# Servo_Controller_Board.net
KiCad netlist of a schematic drawn in Altium Designer
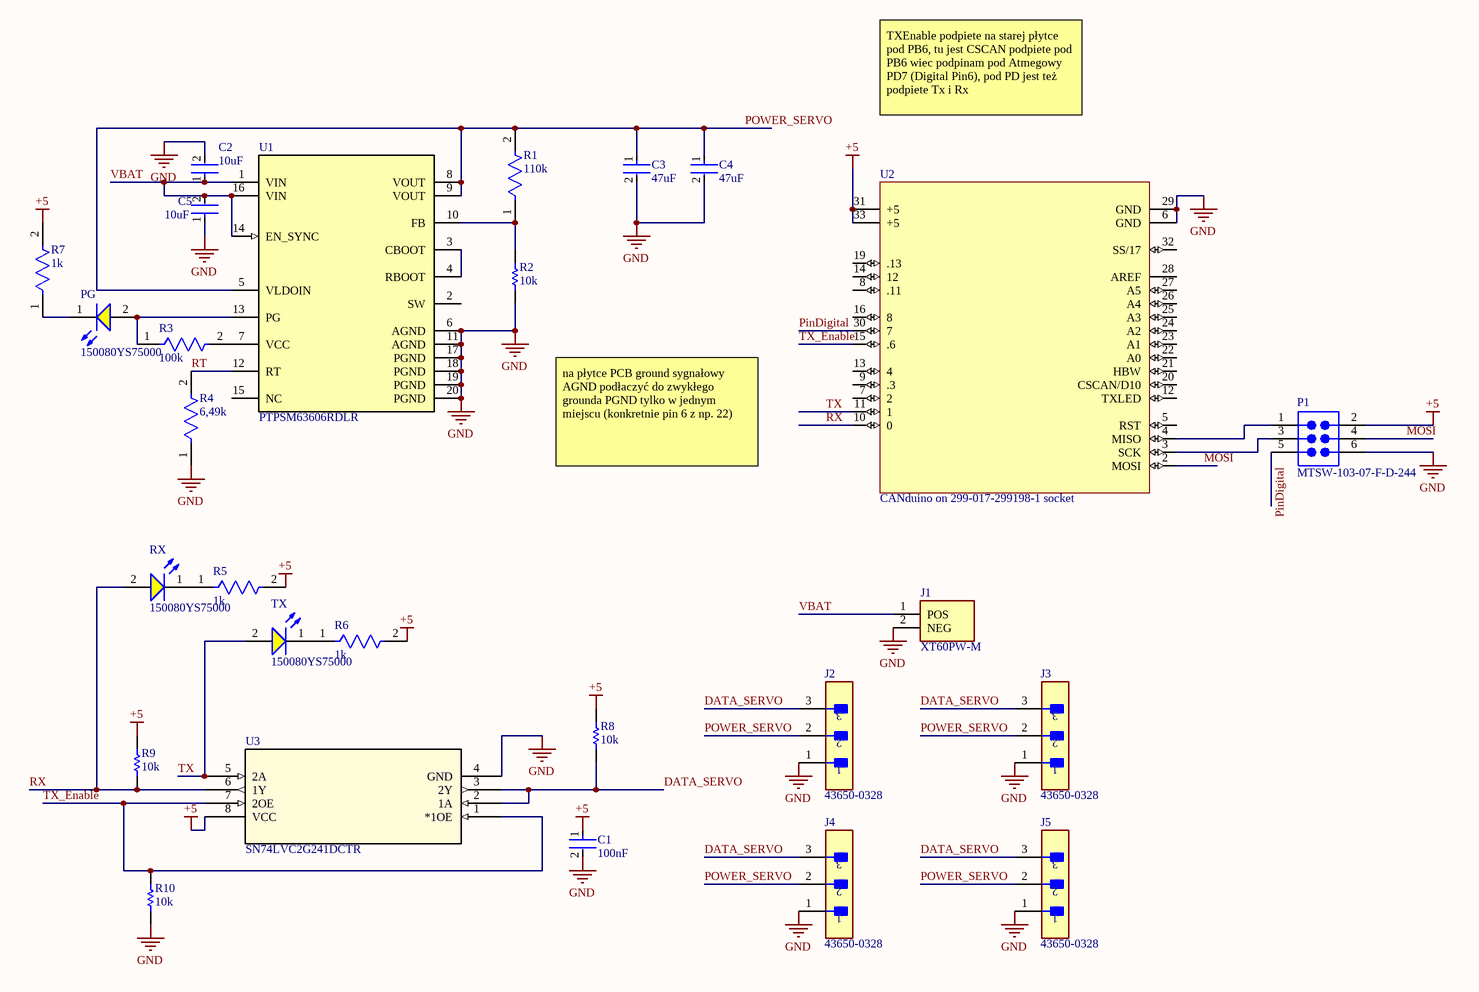
[diagram p0: Servo Controller Board.SchDoc]

(export (version "E")
  (design (tool "Eeschema 10.0.6"))
  (components
    (comp (ref "C1")
      (value "100nF")
      (footprint "FP-0805-L_2_01_0_2-W_1_25-IPC_B")
      (description "Automotive Ceramic Capacitor, 0805, 100nF, 10%, X7R, 15%, 100V")
      (fields (field (name "TOLERANCE") "10%") (field (name "VOLTAGE") "100V"))
      (libsource (lib "Altium Content Vault") (part "b4654b650e69147ec39a6b967a45e02"))
    )
    (comp (ref "C2")
      (value "10uF")
      (footprint "FP-CL32-IPC_A")
      (description "Cap Ceramic 10uF 35V X7R ±10% SMD 1210 +125°C Embossed T/R")
      (fields (field (name "VOLTAGE") "35V") (field (name "TOLERANCE") "10%"))
      (libsource (lib "Altium Content Vault") (part "b4654b650e69147ec39a6b967a45e02"))
    )
    (comp (ref "C3")
      (value "47uF")
      (footprint "FP-GRM32E-0_3-0_2-IPC_A")
      (description "Chip Multilayer Ceramic Capacitors for General Purpose, 1210, 47uF, X6S, 22%, 10%, 16V")
      (fields (field (name "VOLTAGE") "16V") (field (name "TOLERANCE") "10%"))
      (libsource (lib "Altium Content Vault") (part "02cd4be3c70576c341d710602a673aa"))
    )
    (comp (ref "C4")
      (value "47uF")
      (footprint "FP-GRM32E-0_3-0_2-IPC_A")
      (description "Chip Multilayer Ceramic Capacitors for General Purpose, 1210, 47uF, X6S, 22%, 10%, 16V")
      (fields (field (name "VOLTAGE") "16V") (field (name "TOLERANCE") "10%"))
      (libsource (lib "Altium Content Vault") (part "02cd4be3c70576c341d710602a673aa"))
    )
    (comp (ref "C5")
      (value "10uF")
      (footprint "FP-CL32-IPC_A")
      (description "Cap Ceramic 10uF 35V X7R ±10% SMD 1210 +125°C Embossed T/R")
      (fields (field (name "VOLTAGE") "35V") (field (name "TOLERANCE") "10%"))
      (libsource (lib "Altium Content Vault") (part "b4654b650e69147ec39a6b967a45e02"))
    )
    (comp (ref "J1")
      (value "XT60PW-M")
      (footprint "AMASS_XT60PW-M:AMASS_XT60PW-M")
      (description "Socket, DC supply, male, PIN: 2")
      (fields (field (name "MF") "AMASS"))
      (libsource (lib "XT60PW-M") (part "XT60PW-M"))
    )
    (comp (ref "J2")
      (value "43650-0328")
      (footprint "FP-43650-0328-MFG")
      (description "43650-0328 Connector Header HDR 3 POS 3mm Solder ST Thru-Hole 3 Terminal 1 Port Micro-Fit 3.0 Tray")
      (libsource (lib "Altium Content Vault") (part "0d3f023dd272f625e17a2be33dea85f"))
    )
    (comp (ref "J3")
      (value "43650-0328")
      (footprint "FP-43650-0328-MFG")
      (description "43650-0328 Connector Header HDR 3 POS 3mm Solder ST Thru-Hole 3 Terminal 1 Port Micro-Fit 3.0 Tray")
      (libsource (lib "Altium Content Vault") (part "0d3f023dd272f625e17a2be33dea85f"))
    )
    (comp (ref "J4")
      (value "43650-0328")
      (footprint "FP-43650-0328-MFG")
      (description "43650-0328 Connector Header HDR 3 POS 3mm Solder ST Thru-Hole 3 Terminal 1 Port Micro-Fit 3.0 Tray")
      (libsource (lib "Altium Content Vault") (part "0d3f023dd272f625e17a2be33dea85f"))
    )
    (comp (ref "J5")
      (value "43650-0328")
      (footprint "FP-43650-0328-MFG")
      (description "43650-0328 Connector Header HDR 3 POS 3mm Solder ST Thru-Hole 3 Terminal 1 Port Micro-Fit 3.0 Tray")
      (libsource (lib "Altium Content Vault") (part "0d3f023dd272f625e17a2be33dea85f"))
    )
    (comp (ref "P1")
      (value "MTSW-103-07-F-D-244")
      (footprint "SMTC-MTSW-103-07-X-D-244")
      (fields (field (name "MANUFACTURER") "Samtec"))
      (libsource (lib "Altium Content Vault") (part "SMTC-MTSW-103-07-X-D-244"))
    )
    (comp (ref "PG")
      (value "150080YS75000")
      (footprint "WL-SMCW_0805_150080xx75000")
      (description "2 V Yellow LED 2012 (0805) SMD, Wurth Elektronik WL-SMCW 150080YS75000")
      (libsource (lib "Altium Content Vault") (part "LED_Yellow_2A-1K"))
    )
    (comp (ref "R1")
      (value "110k")
      (footprint "FP-AC0603-IPC_B")
      (description "RES 110KΩ 1.00% 0.1W 0603")
      (fields (field (name "TOLERANCE") "1%"))
      (libsource (lib "Altium Content Vault") (part "1029c3af85768c4190bb7ad29bc67b5"))
    )
    (comp (ref "R2")
      (value "10k")
      (footprint "RESC1608X55X25NL10T15")
      (description "Resistor, 10 KOhm, +/- 5%, 100 mW, -55 to 155 degC, 0603 (1608 Metric), RoHS, Tape and Reel")
      (fields (field (name "MANUFACTURER") "Yageo") (field (name "TOLERANCE") "5%"))
      (libsource (lib "Altium Content Vault") (part "RES-2"))
    )
    (comp (ref "R3")
      (value "100k")
      (footprint "FP-AC0603-IPC_B")
      (description "RES 100KΩ 1.00% 0.1W 0603")
      (fields (field (name "TOLERANCE") "1%"))
      (libsource (lib "Altium Content Vault") (part "1029c3af85768c4190bb7ad29bc67b5"))
    )
    (comp (ref "R4")
      (value "6,49k")
      (footprint "FP-CRCW0603-e3-IPC_B")
      (description "RES Thick Film, 6.49kΩ, 1%, 0.1W, 100ppm/°C, 0603")
      (fields (field (name "TOLERANCE") "1%"))
      (libsource (lib "Altium Content Vault") (part "1029c3af85768c4190bb7ad29bc67b5"))
    )
    (comp (ref "R5")
      (value "1k")
      (footprint "FP-RC0603-0_55-IPC_B")
      (description "RES 1K OHM 1% 1/10W 0603")
      (fields (field (name "TOLERANCE") "1%"))
      (libsource (lib "Altium Content Vault") (part "1029c3af85768c4190bb7ad29bc67b5"))
    )
    (comp (ref "R6")
      (value "1k")
      (footprint "FP-RC0603-0_55-IPC_B")
      (description "RES 1K OHM 1% 1/10W 0603")
      (fields (field (name "TOLERANCE") "1%"))
      (libsource (lib "Altium Content Vault") (part "1029c3af85768c4190bb7ad29bc67b5"))
    )
    (comp (ref "R7")
      (value "1k")
      (footprint "FP-RC0603-0_55-IPC_B")
      (description "RES 1K OHM 1% 1/10W 0603")
      (fields (field (name "TOLERANCE") "1%"))
      (libsource (lib "Altium Content Vault") (part "1029c3af85768c4190bb7ad29bc67b5"))
    )
    (comp (ref "R8")
      (value "10k")
      (footprint "RESC1608X55X25NL10T15")
      (description "Resistor, 10 KOhm, +/- 5%, 100 mW, -55 to 155 degC, 0603 (1608 Metric), RoHS, Tape and Reel")
      (fields (field (name "MANUFACTURER") "Yageo") (field (name "TOLERANCE") "5%"))
      (libsource (lib "Altium Content Vault") (part "RES-2"))
    )
    (comp (ref "R9")
      (value "10k")
      (footprint "RESC1608X55X25NL10T15")
      (description "Resistor, 10 KOhm, +/- 5%, 100 mW, -55 to 155 degC, 0603 (1608 Metric), RoHS, Tape and Reel")
      (fields (field (name "MANUFACTURER") "Yageo") (field (name "TOLERANCE") "5%"))
      (libsource (lib "Altium Content Vault") (part "RES-2"))
    )
    (comp (ref "R10")
      (value "10k")
      (footprint "RESC1608X55X25NL10T15")
      (description "Resistor, 10 KOhm, +/- 5%, 100 mW, -55 to 155 degC, 0603 (1608 Metric), RoHS, Tape and Reel")
      (fields (field (name "MANUFACTURER") "Yageo") (field (name "TOLERANCE") "5%"))
      (libsource (lib "Altium Content Vault") (part "RES-2"))
    )
    (comp (ref "RX")
      (value "150080YS75000")
      (footprint "WL-SMCW_0805_150080xx75000")
      (description "2 V Yellow LED 2012 (0805) SMD, Wurth Elektronik WL-SMCW 150080YS75000")
      (libsource (lib "Altium Content Vault") (part "LED_Yellow_2A-1K"))
    )
    (comp (ref "TX")
      (value "150080YS75000")
      (footprint "WL-SMCW_0805_150080xx75000")
      (description "2 V Yellow LED 2012 (0805) SMD, Wurth Elektronik WL-SMCW 150080YS75000")
      (libsource (lib "Altium Content Vault") (part "LED_Yellow_2A-1K"))
    )
    (comp (ref "U1")
      (value "PTPSM63606RDLR")
      (footprint "RDL0020A-MFG")
      (description "No Description Available")
      (libsource (lib "PTPSM63606RDLR") (part "PTPSM63606RDLR"))
    )
    (comp (ref "U2")
      (value "CANduino on 299-017-299198-1 socket")
      (footprint "CANduino on 299-017-299198-1 socket")
      (description "CANduino board without pins 1, 17, 18 and 34 due to socket specification")
      (libsource (lib "CANduino") (part "CANduino on 299-017-299198-1 socket"))
    )
    (comp (ref "U3")
      (value "SN74LVC2G241DCTR")
      (footprint "DCT8")
      (description "No Description Available")
      (libsource (lib "SN74LVC2G241DCTR") (part "SN74LVC2G241DCTR"))
    )
  )
  (nets
    (net (code "1") (name "+5") (class "Default")
      (node (ref "C1") (pin "1") (pinfunction "1_1") (pintype "passive"))
      (node (ref "P1") (pin "2") (pinfunction "2_2") (pintype "passive"))
      (node (ref "R5") (pin "2") (pinfunction "2_2") (pintype "passive"))
      (node (ref "R6") (pin "2") (pinfunction "2_2") (pintype "passive"))
      (node (ref "R7") (pin "2") (pinfunction "2_2") (pintype "passive"))
      (node (ref "R8") (pin "2") (pinfunction "2_2") (pintype "passive"))
      (node (ref "R9") (pin "2") (pinfunction "2_2") (pintype "passive"))
      (node (ref "U2") (pin "31") (pinfunction "+5_31") (pintype "power_in"))
      (node (ref "U2") (pin "33") (pinfunction "+5_33") (pintype "power_in"))
      (node (ref "U3") (pin "8") (pinfunction "VCC_8") (pintype "power_in"))
    )
    (net (code "2") (name "/DATA_SERVO") (class "Default")
      (node (ref "J2") (pin "3") (pinfunction "3_3") (pintype "passive"))
      (node (ref "J3") (pin "3") (pinfunction "3_3") (pintype "passive"))
      (node (ref "J4") (pin "3") (pinfunction "3_3") (pintype "passive"))
      (node (ref "J5") (pin "3") (pinfunction "3_3") (pintype "passive"))
      (node (ref "R8") (pin "1") (pinfunction "1_1") (pintype "passive"))
      (node (ref "U3") (pin "2") (pinfunction "1A_2") (pintype "input"))
      (node (ref "U3") (pin "3") (pinfunction "2Y_3") (pintype "output"))
    )
    (net (code "3") (name "/MOSI") (class "Default")
      (node (ref "P1") (pin "4") (pinfunction "4_4") (pintype "passive"))
      (node (ref "U2") (pin "2") (pinfunction "MOSI_2") (pintype "bidirectional"))
    )
    (net (code "4") (name "/POWER_SERVO") (class "Default")
      (node (ref "C3") (pin "1") (pinfunction "1_1") (pintype "passive"))
      (node (ref "C4") (pin "1") (pinfunction "1_1") (pintype "passive"))
      (node (ref "J2") (pin "2") (pinfunction "2_2") (pintype "passive"))
      (node (ref "J3") (pin "2") (pinfunction "2_2") (pintype "passive"))
      (node (ref "J4") (pin "2") (pinfunction "2_2") (pintype "passive"))
      (node (ref "J5") (pin "2") (pinfunction "2_2") (pintype "passive"))
      (node (ref "R1") (pin "2") (pinfunction "2_2") (pintype "passive"))
      (node (ref "U1") (pin "5") (pinfunction "VLDOIN_5") (pintype "passive"))
      (node (ref "U1") (pin "8") (pinfunction "VOUT_8") (pintype "passive"))
      (node (ref "U1") (pin "9") (pinfunction "VOUT_9") (pintype "passive"))
    )
    (net (code "5") (name "/PinDigital") (class "Default")
      (node (ref "P1") (pin "5") (pinfunction "5_5") (pintype "passive"))
      (node (ref "U2") (pin "30") (pinfunction "7_30") (pintype "bidirectional"))
    )
    (net (code "6") (name "/RT") (class "Default")
      (node (ref "R4") (pin "2") (pinfunction "2_2") (pintype "passive"))
      (node (ref "U1") (pin "12") (pinfunction "RT_12") (pintype "passive"))
    )
    (net (code "7") (name "/RX") (class "Default")
      (node (ref "R9") (pin "1") (pinfunction "1_1") (pintype "passive"))
      (node (ref "RX") (pin "2") (pinfunction "A_2") (pintype "passive"))
      (node (ref "U2") (pin "10") (pinfunction "0_10") (pintype "bidirectional"))
      (node (ref "U3") (pin "6") (pinfunction "1Y_6") (pintype "output"))
    )
    (net (code "8") (name "/TX") (class "Default")
      (node (ref "TX") (pin "2") (pinfunction "A_2") (pintype "passive"))
      (node (ref "U2") (pin "11") (pinfunction "1_11") (pintype "bidirectional"))
      (node (ref "U3") (pin "5") (pinfunction "2A_5") (pintype "input"))
    )
    (net (code "9") (name "/TX_Enable") (class "Default")
      (node (ref "R10") (pin "2") (pinfunction "2_2") (pintype "passive"))
      (node (ref "U2") (pin "15") (pinfunction ".6_15") (pintype "bidirectional"))
      (node (ref "U3") (pin "1") (pinfunction "*1OE_1") (pintype "input"))
      (node (ref "U3") (pin "7") (pinfunction "2OE_7") (pintype "input"))
    )
    (net (code "10") (name "/VBAT") (class "Default")
      (node (ref "C2") (pin "1") (pinfunction "1_1") (pintype "passive"))
      (node (ref "C5") (pin "2") (pinfunction "2_2") (pintype "passive"))
      (node (ref "J1") (pin "1") (pinfunction "POS_1") (pintype "passive"))
      (node (ref "U1") (pin "1") (pinfunction "VIN_1") (pintype "power_in"))
      (node (ref "U1") (pin "14") (pinfunction "EN_SYNC_14") (pintype "input"))
      (node (ref "U1") (pin "16") (pinfunction "VIN_16") (pintype "power_in"))
    )
    (net (code "11") (name "GND") (class "Default")
      (node (ref "C1") (pin "2") (pinfunction "2_2") (pintype "passive"))
      (node (ref "C2") (pin "2") (pinfunction "2_2") (pintype "passive"))
      (node (ref "C3") (pin "2") (pinfunction "2_2") (pintype "passive"))
      (node (ref "C4") (pin "2") (pinfunction "2_2") (pintype "passive"))
      (node (ref "C5") (pin "1") (pinfunction "1_1") (pintype "passive"))
      (node (ref "J1") (pin "2") (pinfunction "NEG_2") (pintype "passive"))
      (node (ref "J2") (pin "1") (pinfunction "1_1") (pintype "passive"))
      (node (ref "J3") (pin "1") (pinfunction "1_1") (pintype "passive"))
      (node (ref "J4") (pin "1") (pinfunction "1_1") (pintype "passive"))
      (node (ref "J5") (pin "1") (pinfunction "1_1") (pintype "passive"))
      (node (ref "P1") (pin "6") (pinfunction "6_6") (pintype "passive"))
      (node (ref "R10") (pin "1") (pinfunction "1_1") (pintype "passive"))
      (node (ref "R2") (pin "1") (pinfunction "1_1") (pintype "passive"))
      (node (ref "R4") (pin "1") (pinfunction "1_1") (pintype "passive"))
      (node (ref "U1") (pin "11") (pinfunction "AGND_11") (pintype "power_in"))
      (node (ref "U1") (pin "17") (pinfunction "PGND_17") (pintype "power_in"))
      (node (ref "U1") (pin "18") (pinfunction "PGND_18") (pintype "power_in"))
      (node (ref "U1") (pin "19") (pinfunction "PGND_19") (pintype "power_in"))
      (node (ref "U1") (pin "20") (pinfunction "PGND_20") (pintype "power_in"))
      (node (ref "U1") (pin "6") (pinfunction "AGND_6") (pintype "power_in"))
      (node (ref "U2") (pin "29") (pinfunction "GND_29") (pintype "passive"))
      (node (ref "U2") (pin "6") (pinfunction "GND_6") (pintype "passive"))
      (node (ref "U3") (pin "4") (pinfunction "GND_4") (pintype "power_in"))
    )
    (net (code "12") (name "Net-(PG-A)") (class "Default")
      (node (ref "PG") (pin "2") (pinfunction "A_2") (pintype "passive"))
      (node (ref "R3") (pin "1") (pinfunction "1_1") (pintype "passive"))
      (node (ref "U1") (pin "13") (pinfunction "PG_13") (pintype "open_collector"))
    )
    (net (code "13") (name "Net-(PG-K)") (class "Default")
      (node (ref "PG") (pin "1") (pinfunction "K_1") (pintype "passive"))
      (node (ref "R7") (pin "1") (pinfunction "1_1") (pintype "passive"))
    )
    (net (code "14") (name "Net-(RX-K)") (class "Default")
      (node (ref "R5") (pin "1") (pinfunction "1_1") (pintype "passive"))
      (node (ref "RX") (pin "1") (pinfunction "K_1") (pintype "passive"))
    )
    (net (code "15") (name "Net-(TX-K)") (class "Default")
      (node (ref "R6") (pin "1") (pinfunction "1_1") (pintype "passive"))
      (node (ref "TX") (pin "1") (pinfunction "K_1") (pintype "passive"))
    )
    (net (code "16") (name "Net-(U1-CBOOT)") (class "Default")
      (node (ref "U1") (pin "3") (pinfunction "CBOOT_3") (pintype "passive"))
      (node (ref "U1") (pin "4") (pinfunction "RBOOT_4") (pintype "passive"))
    )
    (net (code "17") (name "Net-(U1-FB)") (class "Default")
      (node (ref "R1") (pin "1") (pinfunction "1_1") (pintype "passive"))
      (node (ref "R2") (pin "2") (pinfunction "2_2") (pintype "passive"))
      (node (ref "U1") (pin "10") (pinfunction "FB_10") (pintype "passive"))
    )
    (net (code "18") (name "Net-(U1-VCC)") (class "Default")
      (node (ref "R3") (pin "2") (pinfunction "2_2") (pintype "passive"))
      (node (ref "U1") (pin "7") (pinfunction "VCC_7") (pintype "passive"))
    )
    (net (code "19") (name "Net-(U2-MISO)") (class "Default")
      (node (ref "P1") (pin "1") (pinfunction "1_1") (pintype "passive"))
      (node (ref "U2") (pin "4") (pinfunction "MISO_4") (pintype "bidirectional"))
    )
    (net (code "20") (name "Net-(U2-SCK)") (class "Default")
      (node (ref "P1") (pin "3") (pinfunction "3_3") (pintype "passive"))
      (node (ref "U2") (pin "3") (pinfunction "SCK_3") (pintype "bidirectional"))
    )
    (net (code "21") (name "unconnected-(U1-NC-Pad15)") (class "Default")
      (node (ref "U1") (pin "15") (pinfunction "NC_15") (pintype "passive"))
    )
    (net (code "22") (name "unconnected-(U1-SW-Pad2)") (class "Default")
      (node (ref "U1") (pin "2") (pinfunction "SW_2") (pintype "passive"))
    )
    (net (code "23") (name "unconnected-(U2-.3-Pad9)") (class "Default")
      (node (ref "U2") (pin "9") (pinfunction ".3_9") (pintype "bidirectional"))
    )
    (net (code "24") (name "unconnected-(U2-.11-Pad8)") (class "Default")
      (node (ref "U2") (pin "8") (pinfunction ".11_8") (pintype "bidirectional"))
    )
    (net (code "25") (name "unconnected-(U2-.13-Pad19)") (class "Default")
      (node (ref "U2") (pin "19") (pinfunction ".13_19") (pintype "bidirectional"))
    )
    (net (code "26") (name "unconnected-(U2-2-Pad7)") (class "Default")
      (node (ref "U2") (pin "7") (pinfunction "2_7") (pintype "bidirectional"))
    )
    (net (code "27") (name "unconnected-(U2-4-Pad13)") (class "Default")
      (node (ref "U2") (pin "13") (pinfunction "4_13") (pintype "bidirectional"))
    )
    (net (code "28") (name "unconnected-(U2-8-Pad16)") (class "Default")
      (node (ref "U2") (pin "16") (pinfunction "8_16") (pintype "bidirectional"))
    )
    (net (code "29") (name "unconnected-(U2-12-Pad14)") (class "Default")
      (node (ref "U2") (pin "14") (pinfunction "12_14") (pintype "bidirectional"))
    )
    (net (code "30") (name "unconnected-(U2-A0-Pad22)") (class "Default")
      (node (ref "U2") (pin "22") (pinfunction "A0_22") (pintype "bidirectional"))
    )
    (net (code "31") (name "unconnected-(U2-A1-Pad23)") (class "Default")
      (node (ref "U2") (pin "23") (pinfunction "A1_23") (pintype "bidirectional"))
    )
    (net (code "32") (name "unconnected-(U2-A2-Pad24)") (class "Default")
      (node (ref "U2") (pin "24") (pinfunction "A2_24") (pintype "bidirectional"))
    )
    (net (code "33") (name "unconnected-(U2-A3-Pad25)") (class "Default")
      (node (ref "U2") (pin "25") (pinfunction "A3_25") (pintype "bidirectional"))
    )
    (net (code "34") (name "unconnected-(U2-A4-Pad26)") (class "Default")
      (node (ref "U2") (pin "26") (pinfunction "A4_26") (pintype "bidirectional"))
    )
    (net (code "35") (name "unconnected-(U2-A5-Pad27)") (class "Default")
      (node (ref "U2") (pin "27") (pinfunction "A5_27") (pintype "bidirectional"))
    )
    (net (code "36") (name "unconnected-(U2-AREF-Pad28)") (class "Default")
      (node (ref "U2") (pin "28") (pinfunction "AREF_28") (pintype "passive"))
    )
    (net (code "37") (name "unconnected-(U2-CSCAN{slash}D10-Pad20)") (class "Default")
      (node (ref "U2") (pin "20") (pinfunction "CSCAN/D10_20") (pintype "bidirectional"))
    )
    (net (code "38") (name "unconnected-(U2-HBW-Pad21)") (class "Default")
      (node (ref "U2") (pin "21") (pinfunction "HBW_21") (pintype "bidirectional"))
    )
    (net (code "39") (name "unconnected-(U2-RST-Pad5)") (class "Default")
      (node (ref "U2") (pin "5") (pinfunction "RST_5") (pintype "bidirectional"))
    )
    (net (code "40") (name "unconnected-(U2-SS{slash}17-Pad32)") (class "Default")
      (node (ref "U2") (pin "32") (pinfunction "SS/17_32") (pintype "bidirectional"))
    )
    (net (code "41") (name "unconnected-(U2-TXLED-Pad12)") (class "Default")
      (node (ref "U2") (pin "12") (pinfunction "TXLED_12") (pintype "bidirectional"))
    )
  )
)
